# SCH_BEL_RUMAH.net
KiCad netlist of a schematic drawn in EAGLE
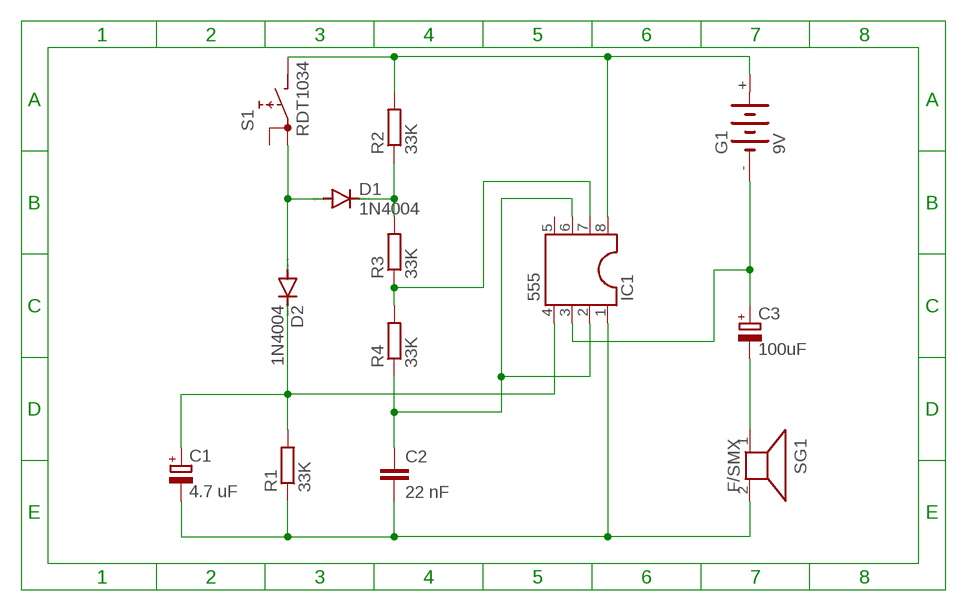
[diagram p0: schematic, sheet 1]

(export (version "E")
  (design (tool "Eeschema 10.0.6"))
  (components
    (comp (ref "C1")
      (value "4.7 uF")
      (footprint "eagle-import:TT2D5")
      (libsource (lib "eagle-import") (part "CPOL-EUTT2D5"))
    )
    (comp (ref "C2")
      (value "22 nF")
      (footprint "eagle-import:C025-024X044")
      (libsource (lib "eagle-import") (part "C-EU025-024X044"))
    )
    (comp (ref "C3")
      (value "100uF")
      (footprint "eagle-import:TT2D5")
      (libsource (lib "eagle-import") (part "CPOL-EUTT2D5"))
    )
    (comp (ref "D1")
      (value "1N4004")
      (footprint "eagle-import:DO41-10")
      (libsource (lib "eagle-import") (part "1N4004"))
    )
    (comp (ref "D2")
      (value "1N4004")
      (footprint "eagle-import:DO41-10")
      (libsource (lib "eagle-import") (part "1N4004"))
    )
    (comp (ref "G1")
      (value "9V")
      (footprint "eagle-import:3V11R")
      (libsource (lib "eagle-import") (part "3V11R"))
    )
    (comp (ref "IC1")
      (value "555")
      (footprint "eagle-import:DIL08")
      (libsource (lib "eagle-import") (part "DIL8"))
    )
    (comp (ref "R1")
      (value "33K")
      (footprint "eagle-import:0204_7")
      (libsource (lib "eagle-import") (part "R-EU_0204/7"))
    )
    (comp (ref "R2")
      (value "33K")
      (footprint "eagle-import:0204_7")
      (libsource (lib "eagle-import") (part "R-EU_0204/7"))
    )
    (comp (ref "R3")
      (value "33K")
      (footprint "eagle-import:0204_7")
      (libsource (lib "eagle-import") (part "R-EU_0204/7"))
    )
    (comp (ref "R4")
      (value "33K")
      (footprint "eagle-import:0204_7")
      (libsource (lib "eagle-import") (part "R-EU_0204/7"))
    )
    (comp (ref "S1")
      (value "RDT1034")
      (footprint "eagle-import:RDT1034")
      (libsource (lib "eagle-import") (part "RDT1034"))
    )
    (comp (ref "SG1")
      (value "F/SMX")
      (footprint "eagle-import:F_SMX")
      (libsource (lib "eagle-import") (part "F/SMX"))
    )
  )
  (nets
    (net (code "1") (name "Net-(C1-Pad+)") (class "Default")
      (node (ref "C1") (pin "+") (pinfunction "+_+") (pintype "passive"))
      (node (ref "D2") (pin "C") (pinfunction "C_C") (pintype "passive"))
      (node (ref "IC1") (pin "4") (pinfunction "4_4") (pintype "passive"))
      (node (ref "R1") (pin "2") (pinfunction "2_2") (pintype "passive"))
    )
    (net (code "2") (name "Net-(C1-Pad-)") (class "Default")
      (node (ref "C1") (pin "-") (pinfunction "-_-") (pintype "passive"))
      (node (ref "C2") (pin "2") (pinfunction "2_2") (pintype "passive"))
      (node (ref "IC1") (pin "1") (pinfunction "1_1") (pintype "passive"))
      (node (ref "R1") (pin "1") (pinfunction "1_1") (pintype "passive"))
      (node (ref "SG1") (pin "2") (pinfunction "2_2") (pintype "passive"))
    )
    (net (code "3") (name "Net-(C2-Pad1)") (class "Default")
      (node (ref "C2") (pin "1") (pinfunction "1_1") (pintype "passive"))
      (node (ref "IC1") (pin "2") (pinfunction "2_2") (pintype "passive"))
      (node (ref "IC1") (pin "6") (pinfunction "6_6") (pintype "passive"))
      (node (ref "R4") (pin "1") (pinfunction "1_1") (pintype "passive"))
    )
    (net (code "4") (name "Net-(C3-Pad+)") (class "Default")
      (node (ref "C3") (pin "+") (pinfunction "+_+") (pintype "passive"))
      (node (ref "G1") (pin "-") (pinfunction "-_-") (pintype "passive"))
      (node (ref "IC1") (pin "3") (pinfunction "3_3") (pintype "passive"))
    )
    (net (code "5") (name "Net-(C3-Pad-)") (class "Default")
      (node (ref "C3") (pin "-") (pinfunction "-_-") (pintype "passive"))
      (node (ref "SG1") (pin "1") (pinfunction "1_1") (pintype "passive"))
    )
    (net (code "6") (name "Net-(D1-PadA)") (class "Default")
      (node (ref "D1") (pin "A") (pinfunction "A_A") (pintype "passive"))
      (node (ref "D2") (pin "A") (pinfunction "A_A") (pintype "passive"))
      (node (ref "S1") (pin "A1") (pinfunction "A1_A1") (pintype "passive"))
    )
    (net (code "7") (name "Net-(D1-PadC)") (class "Default")
      (node (ref "D1") (pin "C") (pinfunction "C_C") (pintype "passive"))
      (node (ref "R2") (pin "1") (pinfunction "1_1") (pintype "passive"))
      (node (ref "R3") (pin "2") (pinfunction "2_2") (pintype "passive"))
    )
    (net (code "8") (name "Net-(G1-Pad+)") (class "Default")
      (node (ref "G1") (pin "+") (pinfunction "+_+") (pintype "passive"))
      (node (ref "IC1") (pin "8") (pinfunction "8_8") (pintype "passive"))
      (node (ref "R2") (pin "2") (pinfunction "2_2") (pintype "passive"))
      (node (ref "S1") (pin "B") (pinfunction "B_B") (pintype "passive"))
    )
    (net (code "9") (name "Net-(IC1-Pad7)") (class "Default")
      (node (ref "IC1") (pin "7") (pinfunction "7_7") (pintype "passive"))
      (node (ref "R3") (pin "1") (pinfunction "1_1") (pintype "passive"))
      (node (ref "R4") (pin "2") (pinfunction "2_2") (pintype "passive"))
    )
    (net (code "10") (name "unconnected-(IC1-Pad5)") (class "Default")
      (node (ref "IC1") (pin "5") (pinfunction "5_5") (pintype "passive"))
    )
    (net (code "11") (name "unconnected-(S1-PadA)") (class "Default")
      (node (ref "S1") (pin "A") (pinfunction "A_A") (pintype "passive"))
    )
  )
)
